# spider.net
KiCad netlist of a schematic drawn in Altium Designer
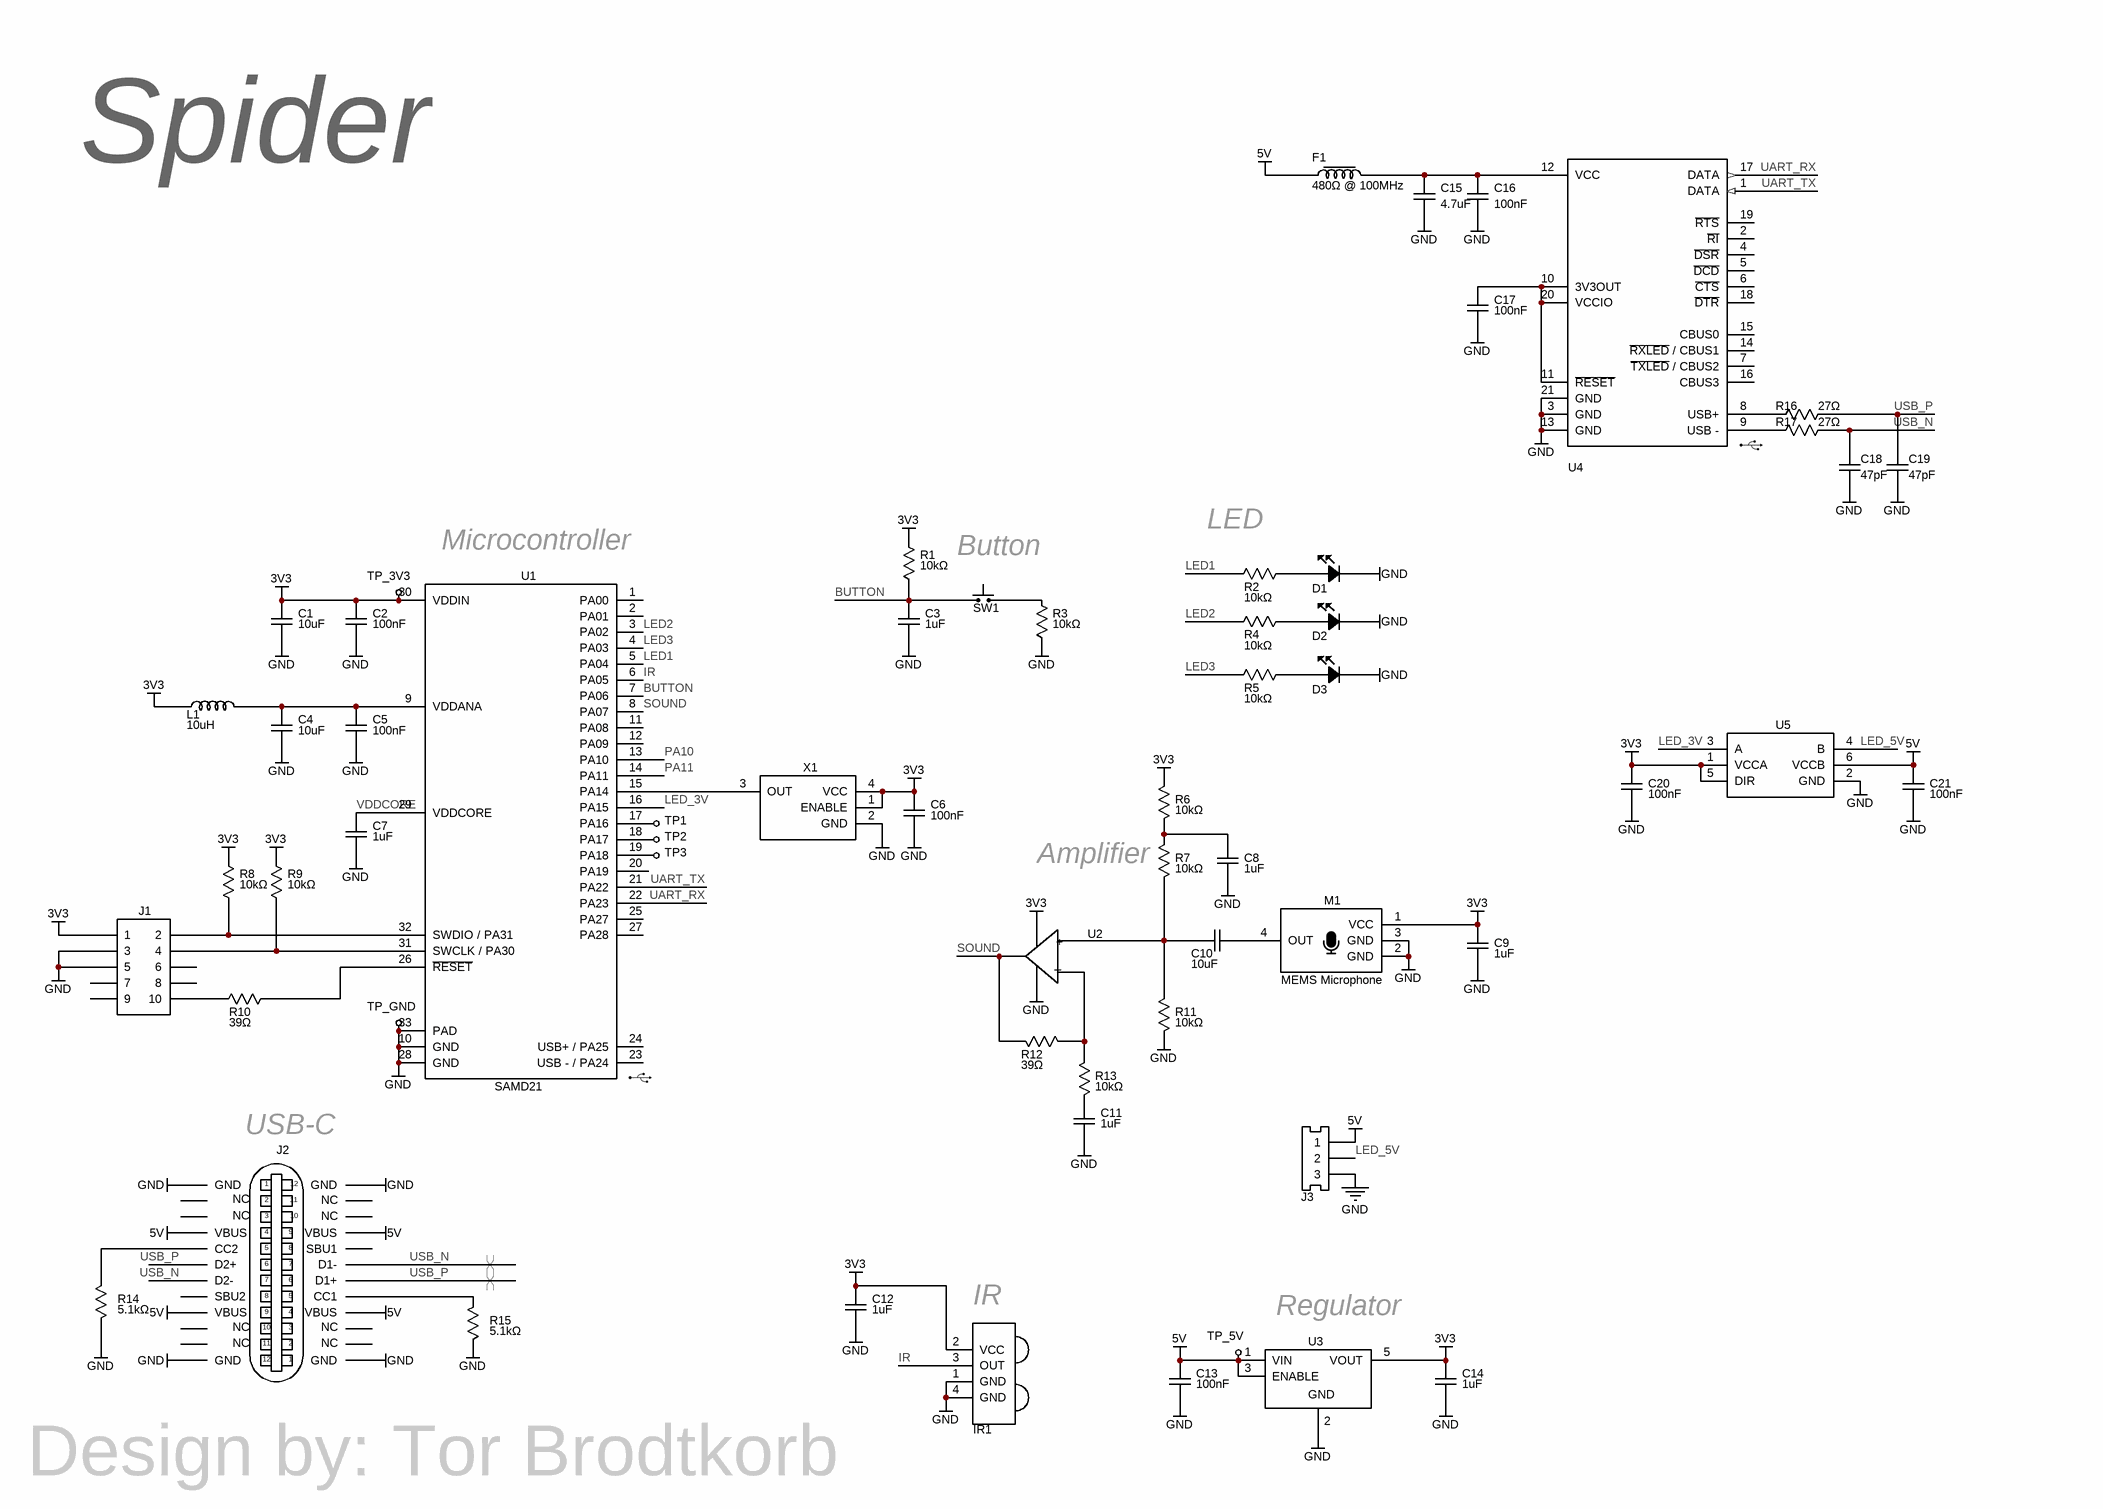
[diagram p0: spider.SchDoc]

(export (version "E")
  (design (tool "Eeschema 10.0.6"))
  (components
    (comp (ref "C1")
      (value "10uF")
      (footprint "capacitor 0603")
      (description "Capacitor 0603")
      (fields (field (name "Comment") "passive_5"))
      (libsource (lib "passive") (part "passive_5"))
    )
    (comp (ref "C2")
      (value "100nF")
      (footprint "capacitor 0603")
      (description "Capacitor 0603")
      (fields (field (name "Comment") "passive_5"))
      (libsource (lib "passive") (part "passive_5"))
    )
    (comp (ref "C3")
      (value "1uF")
      (footprint "capacitor 0603")
      (description "Capacitor 0603")
      (fields (field (name "Comment") "passive_5"))
      (libsource (lib "passive") (part "passive_5"))
    )
    (comp (ref "C4")
      (value "10uF")
      (footprint "capacitor 0603")
      (description "Capacitor 0603")
      (fields (field (name "Comment") "passive_5"))
      (libsource (lib "passive") (part "passive_5"))
    )
    (comp (ref "C5")
      (value "100nF")
      (footprint "capacitor 0603")
      (description "Capacitor 0603")
      (fields (field (name "Comment") "passive_5"))
      (libsource (lib "passive") (part "passive_5"))
    )
    (comp (ref "C6")
      (value "100nF")
      (footprint "capacitor 0603")
      (description "Capacitor 0603")
      (fields (field (name "Comment") "passive_5"))
      (libsource (lib "passive") (part "passive_5"))
    )
    (comp (ref "C7")
      (value "1uF")
      (footprint "capacitor 0603")
      (description "Capacitor 0603")
      (fields (field (name "Comment") "passive_5"))
      (libsource (lib "passive") (part "passive_5"))
    )
    (comp (ref "C8")
      (value "1uF")
      (footprint "capacitor 0603")
      (description "Capacitor 0603")
      (fields (field (name "Comment") "passive_5"))
      (libsource (lib "passive") (part "passive_5"))
    )
    (comp (ref "C9")
      (value "1uF")
      (footprint "capacitor 0603")
      (description "Capacitor 0603")
      (fields (field (name "Comment") "passive_5"))
      (libsource (lib "passive") (part "passive_5"))
    )
    (comp (ref "C10")
      (value "10uF")
      (footprint "capacitor 0603")
      (description "Capacitor 0603")
      (fields (field (name "Comment") "passive_5"))
      (libsource (lib "passive") (part "passive_5"))
    )
    (comp (ref "C11")
      (value "1uF")
      (footprint "capacitor 0603")
      (description "Capacitor 0603")
      (fields (field (name "Comment") "passive_5"))
      (libsource (lib "passive") (part "passive_5"))
    )
    (comp (ref "C12")
      (value "1uF")
      (footprint "capacitor 0603")
      (description "Capacitor 0603")
      (fields (field (name "Comment") "passive_5"))
      (libsource (lib "passive") (part "passive_5"))
    )
    (comp (ref "C13")
      (value "100nF")
      (footprint "capacitor 0603")
      (description "Capacitor 0603")
      (fields (field (name "Comment") "passive_5"))
      (libsource (lib "passive") (part "passive_5"))
    )
    (comp (ref "C14")
      (value "1uF")
      (footprint "capacitor 0603")
      (description "Capacitor 0603")
      (fields (field (name "Comment") "passive_5"))
      (libsource (lib "passive") (part "passive_5"))
    )
    (comp (ref "C15")
      (value "4.7uF")
      (footprint "capacitor 0603")
      (description "Capacitor 0603")
      (fields (field (name "Comment") "passive_5"))
      (libsource (lib "passive") (part "passive_5"))
    )
    (comp (ref "C16")
      (value "100nF")
      (footprint "capacitor 0603")
      (description "Capacitor 0603")
      (fields (field (name "Comment") "passive_5"))
      (libsource (lib "passive") (part "passive_5"))
    )
    (comp (ref "C17")
      (value "100nF")
      (footprint "capacitor 0603")
      (description "Capacitor 0603")
      (fields (field (name "Comment") "passive_5"))
      (libsource (lib "passive") (part "passive_5"))
    )
    (comp (ref "C18")
      (value "47pF")
      (footprint "capacitor 0603")
      (description "Capacitor 0603")
      (fields (field (name "Comment") "passive_5"))
      (libsource (lib "passive") (part "passive_5"))
    )
    (comp (ref "C19")
      (value "47pF")
      (footprint "capacitor 0603")
      (description "Capacitor 0603")
      (fields (field (name "Comment") "passive_5"))
      (libsource (lib "passive") (part "passive_5"))
    )
    (comp (ref "C20")
      (value "100nF")
      (footprint "capacitor 0603")
      (description "Capacitor 0603")
      (fields (field (name "Comment") "passive_5"))
      (libsource (lib "passive") (part "passive_5"))
    )
    (comp (ref "C21")
      (value "100nF")
      (footprint "capacitor 0603")
      (description "Capacitor 0603")
      (fields (field (name "Comment") "passive_5"))
      (libsource (lib "passive") (part "passive_5"))
    )
    (comp (ref "D1")
      (value "LED White")
      (footprint "LED 0603 white")
      (description "LED 0603 white")
      (libsource (lib "diode") (part "diode_6"))
    )
    (comp (ref "D2")
      (value "LED White")
      (footprint "LED 0603 white")
      (description "LED 0603 white")
      (libsource (lib "diode") (part "diode_6"))
    )
    (comp (ref "D3")
      (value "LED White")
      (footprint "LED 0603 white")
      (description "LED 0603 white")
      (libsource (lib "diode") (part "diode_6"))
    )
    (comp (ref "F1")
      (value "480Ω @ 100MHz")
      (footprint "ferrit bead 0603")
      (description "Ferrite bead 0603")
      (fields (field (name "Comment") "passive_8"))
      (libsource (lib "passive") (part "passive_8"))
    )
    (comp (ref "IR1")
      (value "sensor_1")
      (footprint "TSSP77038TR")
      (description "IR receiver, 38 kHz, 40m, SMD")
      (libsource (lib "sensor") (part "sensor_1"))
    )
    (comp (ref "J1")
      (value "Header 1.27mm")
      (footprint "header male 2x5, pitch 1.27mm")
      (description "Header male 2x5, pitch 1.27mm")
      (libsource (lib "connector") (part "connector_17"))
    )
    (comp (ref "J2")
      (value "USB 2.0")
      (footprint "USB4105-GF-A")
      (description "USB-C (2.0)")
      (libsource (lib "connector") (part "connector_35"))
    )
    (comp (ref "J3")
      (value "connector_41")
      (footprint "S3B-XH-A (LF)(SN)")
      (description "JST connector 1x3, pitch 2.5mm, right angle, TH")
      (libsource (lib "connector") (part "connector_41"))
    )
    (comp (ref "L1")
      (value "10uH")
      (footprint "inductor 0603")
      (description "Inductor 0603")
      (fields (field (name "Comment") "passive_9"))
      (libsource (lib "passive") (part "passive_9"))
    )
    (comp (ref "M1")
      (value "MEMS Microphone")
      (footprint "SPU0410HR5H-PB")
      (description "Microphone, MEMS, 100 Hz - 10 kHz, 3.3V,  SMD")
      (libsource (lib "sensor") (part "sensor_2"))
    )
    (comp (ref "R1")
      (value "10kΩ")
      (footprint "resistor 0603")
      (description "Resistor 0603")
      (fields (field (name "Comment") "passive_2"))
      (libsource (lib "passive") (part "passive_2"))
    )
    (comp (ref "R2")
      (value "10kΩ")
      (footprint "resistor 0603")
      (description "Resistor 0603")
      (fields (field (name "Comment") "passive_2"))
      (libsource (lib "passive") (part "passive_2"))
    )
    (comp (ref "R3")
      (value "10kΩ")
      (footprint "resistor 0603")
      (description "Resistor 0603")
      (fields (field (name "Comment") "passive_2"))
      (libsource (lib "passive") (part "passive_2"))
    )
    (comp (ref "R4")
      (value "10kΩ")
      (footprint "resistor 0603")
      (description "Resistor 0603")
      (fields (field (name "Comment") "passive_2"))
      (libsource (lib "passive") (part "passive_2"))
    )
    (comp (ref "R5")
      (value "10kΩ")
      (footprint "resistor 0603")
      (description "Resistor 0603")
      (fields (field (name "Comment") "passive_2"))
      (libsource (lib "passive") (part "passive_2"))
    )
    (comp (ref "R6")
      (value "10kΩ")
      (footprint "resistor 0603")
      (description "Resistor 0603")
      (fields (field (name "Comment") "passive_2"))
      (libsource (lib "passive") (part "passive_2"))
    )
    (comp (ref "R7")
      (value "10kΩ")
      (footprint "resistor 0603")
      (description "Resistor 0603")
      (fields (field (name "Comment") "passive_2"))
      (libsource (lib "passive") (part "passive_2"))
    )
    (comp (ref "R8")
      (value "10kΩ")
      (footprint "resistor 0603")
      (description "Resistor 0603")
      (fields (field (name "Comment") "passive_2"))
      (libsource (lib "passive") (part "passive_2"))
    )
    (comp (ref "R9")
      (value "10kΩ")
      (footprint "resistor 0603")
      (description "Resistor 0603")
      (fields (field (name "Comment") "passive_2"))
      (libsource (lib "passive") (part "passive_2"))
    )
    (comp (ref "R10")
      (value "39Ω")
      (footprint "resistor 0603")
      (description "Resistor 0603")
      (fields (field (name "Comment") "passive_2"))
      (libsource (lib "passive") (part "passive_2"))
    )
    (comp (ref "R11")
      (value "10kΩ")
      (footprint "resistor 0603")
      (description "Resistor 0603")
      (fields (field (name "Comment") "passive_2"))
      (libsource (lib "passive") (part "passive_2"))
    )
    (comp (ref "R12")
      (value "39Ω")
      (footprint "resistor 0603")
      (description "Resistor 0603")
      (fields (field (name "Comment") "passive_2"))
      (libsource (lib "passive") (part "passive_2"))
    )
    (comp (ref "R13")
      (value "10kΩ")
      (footprint "resistor 0603")
      (description "Resistor 0603")
      (fields (field (name "Comment") "passive_2"))
      (libsource (lib "passive") (part "passive_2"))
    )
    (comp (ref "R14")
      (value "5.1kΩ")
      (footprint "resistor 0603")
      (description "Resistor 0603")
      (fields (field (name "Comment") "passive_2"))
      (libsource (lib "passive") (part "passive_2"))
    )
    (comp (ref "R15")
      (value "5.1kΩ")
      (footprint "resistor 0603")
      (description "Resistor 0603")
      (fields (field (name "Comment") "passive_2"))
      (libsource (lib "passive") (part "passive_2"))
    )
    (comp (ref "R16")
      (value "27Ω")
      (footprint "resistor 0603")
      (description "Resistor 0603")
      (fields (field (name "Comment") "passive_2"))
      (libsource (lib "passive") (part "passive_2"))
    )
    (comp (ref "R17")
      (value "27Ω")
      (footprint "resistor 0603")
      (description "Resistor 0603")
      (fields (field (name "Comment") "passive_2"))
      (libsource (lib "passive") (part "passive_2"))
    )
    (comp (ref "SW1")
      (value "connector_35")
      (footprint "KMR621NG LFS")
      (description "Tactile switch SMD, tiny")
      (libsource (lib "sensor") (part "connector_35"))
    )
    (comp (ref "TP1")
      (value "misc_3")
      (footprint "testpoint round, diameter 1.5mm")
      (description "Test-point round, diameter 1.5mm")
      (libsource (lib "miscellaneous") (part "misc_3"))
    )
    (comp (ref "TP2")
      (value "misc_3")
      (footprint "testpoint round, diameter 1.5mm")
      (description "Test-point round, diameter 1.5mm")
      (libsource (lib "miscellaneous") (part "misc_3"))
    )
    (comp (ref "TP3")
      (value "misc_3")
      (footprint "testpoint round, diameter 1.5mm")
      (description "Test-point round, diameter 1.5mm")
      (libsource (lib "miscellaneous") (part "misc_3"))
    )
    (comp (ref "TP_3V3")
      (value "misc_3")
      (footprint "testpoint round, diameter 1.5mm")
      (description "Test-point round, diameter 1.5mm")
      (libsource (lib "miscellaneous") (part "misc_3"))
    )
    (comp (ref "TP_5V")
      (value "misc_3")
      (footprint "testpoint round, diameter 1.5mm")
      (description "Test-point round, diameter 1.5mm")
      (libsource (lib "miscellaneous") (part "misc_3"))
    )
    (comp (ref "TP_GND")
      (value "misc_3")
      (footprint "testpoint round, diameter 1.5mm")
      (description "Test-point round, diameter 1.5mm")
      (libsource (lib "miscellaneous") (part "misc_3"))
    )
    (comp (ref "U1")
      (value "SAMD21")
      (footprint "ATSAMD21E17D-MUT")
      (description "SAMD21, 48 MHz, 128KB flash, 16KB RAM, 32 pins, USB device, QFN")
      (libsource (lib "cpu") (part "cpu_0"))
    )
    (comp (ref "U2")
      (value "ic_6")
      (footprint "MCP6241T-E/OT")
      (description "OpAmp, 1 circuit, rail-to-rail, single supply, 1.8V to 5V, SOT23-5")
      (libsource (lib "integrated-circuit") (part "ic_6"))
    )
    (comp (ref "U3")
      (value "regulator_1")
      (footprint "TCR2EF33,LM(CT")
      (description "LDO fixed, 3.3V output, 0.2V dropout, 200mA")
      (libsource (lib "voltage-regulator") (part "regulator_1"))
    )
    (comp (ref "U4")
      (value "FTDI")
      (footprint "FT231XQ-R")
      (description "USB to UART converter, FTDI, single, 20 pins, QFN")
      (libsource (lib "integrated-circuit") (part "ic_1"))
    )
    (comp (ref "U5")
      (value "ic_10")
      (footprint "74LVC1T45Z6-7")
      (description "Level shifter, bidirectional, 1.65V - 5V, SOT-563")
      (libsource (lib "integrated-circuit") (part "ic_10"))
    )
    (comp (ref "X1")
      (value "8 MHz")
      (footprint "DSC6001CE2A-008.0000")
      (description "Oscillator, 8MHz, 3.3V, 3.2mm x 2.5mm")
      (libsource (lib "oscillator") (part "oscillator_2"))
    )
  )
  (nets
    (net (code "1") (name "/BUTTON") (class "Default")
      (node (ref "C3") (pin "2") (pinfunction "2_2") (pintype "passive"))
      (node (ref "R1") (pin "2") (pinfunction "2_2") (pintype "passive"))
      (node (ref "SW1") (pin "1") (pintype "passive"))
      (node (ref "U1") (pin "7") (pinfunction "PA06_7") (pintype "passive"))
    )
    (net (code "2") (name "/IR") (class "Default")
      (node (ref "IR1") (pin "3") (pinfunction "OUT_3") (pintype "passive"))
      (node (ref "U1") (pin "6") (pinfunction "PA05_6") (pintype "passive"))
    )
    (net (code "3") (name "/LED1") (class "Default")
      (node (ref "R2") (pin "2") (pinfunction "2_2") (pintype "passive"))
      (node (ref "U1") (pin "5") (pinfunction "PA04_5") (pintype "passive"))
    )
    (net (code "4") (name "/LED2") (class "Default")
      (node (ref "R4") (pin "2") (pinfunction "2_2") (pintype "passive"))
      (node (ref "U1") (pin "3") (pinfunction "PA02_3") (pintype "passive"))
    )
    (net (code "5") (name "/LED3") (class "Default")
      (node (ref "R5") (pin "2") (pinfunction "2_2") (pintype "passive"))
      (node (ref "U1") (pin "4") (pinfunction "PA03_4") (pintype "passive"))
    )
    (net (code "6") (name "/LED_3V") (class "Default")
      (node (ref "U1") (pin "16") (pinfunction "PA15_16") (pintype "passive"))
      (node (ref "U5") (pin "3") (pinfunction "A_3") (pintype "passive"))
    )
    (net (code "7") (name "/LED_5V") (class "Default")
      (node (ref "J3") (pin "2") (pinfunction "2_2") (pintype "passive"))
      (node (ref "U5") (pin "4") (pinfunction "B_4") (pintype "passive"))
    )
    (net (code "8") (name "/PA10") (class "Default")
      (node (ref "U1") (pin "13") (pinfunction "PA10_13") (pintype "passive"))
    )
    (net (code "9") (name "/PA11") (class "Default")
      (node (ref "U1") (pin "14") (pinfunction "PA11_14") (pintype "passive"))
    )
    (net (code "10") (name "/SOUND") (class "Default")
      (node (ref "R12") (pin "2") (pinfunction "2_2") (pintype "passive"))
      (node (ref "U1") (pin "8") (pinfunction "PA07_8") (pintype "passive"))
      (node (ref "U2") (pin "1") (pintype "passive"))
    )
    (net (code "11") (name "/UART_RX") (class "Default")
      (node (ref "U1") (pin "22") (pinfunction "PA23_22") (pintype "passive"))
      (node (ref "U4") (pin "17") (pinfunction "DATA_17") (pintype "passive"))
    )
    (net (code "12") (name "/UART_TX") (class "Default")
      (node (ref "U1") (pin "21") (pinfunction "PA22_21") (pintype "passive"))
      (node (ref "U4") (pin "1") (pinfunction "DATA_1") (pintype "passive"))
    )
    (net (code "13") (name "/USB_N") (class "Default")
      (node (ref "C18") (pin "2") (pinfunction "2_2") (pintype "passive"))
      (node (ref "J2") (pin "A7") (pinfunction "D1-_A7") (pintype "passive"))
      (node (ref "J2") (pin "B7") (pinfunction "D2-_B7") (pintype "passive"))
      (node (ref "R17") (pin "2") (pinfunction "2_2") (pintype "passive"))
    )
    (net (code "14") (name "/USB_P") (class "Default")
      (node (ref "C19") (pin "2") (pinfunction "2_2") (pintype "passive"))
      (node (ref "J2") (pin "A6") (pinfunction "D1+_A6") (pintype "passive"))
      (node (ref "J2") (pin "B6") (pinfunction "D2+_B6") (pintype "passive"))
      (node (ref "R16") (pin "2") (pinfunction "2_2") (pintype "passive"))
    )
    (net (code "15") (name "/VDDCORE") (class "Default")
      (node (ref "C7") (pin "2") (pinfunction "2_2") (pintype "passive"))
      (node (ref "U1") (pin "29") (pinfunction "VDDCORE_29") (pintype "passive"))
    )
    (net (code "16") (name "3V3") (class "Default")
      (node (ref "C1") (pin "2") (pinfunction "2_2") (pintype "passive"))
      (node (ref "C12") (pin "2") (pinfunction "2_2") (pintype "passive"))
      (node (ref "C14") (pin "2") (pinfunction "2_2") (pintype "passive"))
      (node (ref "C2") (pin "2") (pinfunction "2_2") (pintype "passive"))
      (node (ref "C20") (pin "2") (pinfunction "2_2") (pintype "passive"))
      (node (ref "C6") (pin "2") (pinfunction "2_2") (pintype "passive"))
      (node (ref "C9") (pin "2") (pinfunction "2_2") (pintype "passive"))
      (node (ref "IR1") (pin "2") (pinfunction "VCC_2") (pintype "passive"))
      (node (ref "J1") (pin "1") (pinfunction "1_1") (pintype "passive"))
      (node (ref "L1") (pin "1") (pintype "passive"))
      (node (ref "M1") (pin "1") (pinfunction "VCC_1") (pintype "passive"))
      (node (ref "R1") (pin "1") (pintype "passive"))
      (node (ref "R6") (pin "2") (pinfunction "2_2") (pintype "passive"))
      (node (ref "R8") (pin "2") (pinfunction "2_2") (pintype "passive"))
      (node (ref "R9") (pin "2") (pinfunction "2_2") (pintype "passive"))
      (node (ref "TP_3V3") (pin "1") (pintype "passive"))
      (node (ref "U1") (pin "30") (pinfunction "VDDIN_30") (pintype "passive"))
      (node (ref "U2") (pin "5") (pintype "passive"))
      (node (ref "U3") (pin "5") (pinfunction "VOUT_5") (pintype "passive"))
      (node (ref "U5") (pin "1") (pinfunction "VCCA_1") (pintype "passive"))
      (node (ref "U5") (pin "5") (pinfunction "DIR_5") (pintype "passive"))
      (node (ref "X1") (pin "1") (pinfunction "ENABLE_1") (pintype "passive"))
      (node (ref "X1") (pin "4") (pinfunction "VCC_4") (pintype "passive"))
    )
    (net (code "17") (name "5V") (class "Default")
      (node (ref "C13") (pin "2") (pinfunction "2_2") (pintype "passive"))
      (node (ref "C21") (pin "2") (pinfunction "2_2") (pintype "passive"))
      (node (ref "F1") (pin "1") (pintype "passive"))
      (node (ref "J2") (pin "A4_B9") (pinfunction "VBUS_A4_B9") (pintype "passive"))
      (node (ref "J2") (pin "B4_A9") (pinfunction "VBUS_B4_A9") (pintype "passive"))
      (node (ref "J3") (pin "1") (pinfunction "1_1") (pintype "passive"))
      (node (ref "TP_5V") (pin "1") (pintype "passive"))
      (node (ref "U3") (pin "1") (pinfunction "VIN_1") (pintype "passive"))
      (node (ref "U3") (pin "3") (pinfunction "ENABLE_3") (pintype "passive"))
      (node (ref "U5") (pin "6") (pinfunction "VCCB_6") (pintype "passive"))
    )
    (net (code "18") (name "GND") (class "Default")
      (node (ref "C1") (pin "1") (pinfunction "1_1") (pintype "passive"))
      (node (ref "C11") (pin "1") (pinfunction "1_1") (pintype "passive"))
      (node (ref "C12") (pin "1") (pinfunction "1_1") (pintype "passive"))
      (node (ref "C13") (pin "1") (pinfunction "1_1") (pintype "passive"))
      (node (ref "C14") (pin "1") (pinfunction "1_1") (pintype "passive"))
      (node (ref "C15") (pin "1") (pinfunction "1_1") (pintype "passive"))
      (node (ref "C16") (pin "1") (pinfunction "1_1") (pintype "passive"))
      (node (ref "C17") (pin "1") (pinfunction "1_1") (pintype "passive"))
      (node (ref "C18") (pin "1") (pinfunction "1_1") (pintype "passive"))
      (node (ref "C19") (pin "1") (pinfunction "1_1") (pintype "passive"))
      (node (ref "C2") (pin "1") (pinfunction "1_1") (pintype "passive"))
      (node (ref "C20") (pin "1") (pinfunction "1_1") (pintype "passive"))
      (node (ref "C21") (pin "1") (pinfunction "1_1") (pintype "passive"))
      (node (ref "C3") (pin "1") (pinfunction "1_1") (pintype "passive"))
      (node (ref "C4") (pin "1") (pinfunction "1_1") (pintype "passive"))
      (node (ref "C5") (pin "1") (pinfunction "1_1") (pintype "passive"))
      (node (ref "C6") (pin "1") (pinfunction "1_1") (pintype "passive"))
      (node (ref "C7") (pin "1") (pinfunction "1_1") (pintype "passive"))
      (node (ref "C8") (pin "1") (pinfunction "1_1") (pintype "passive"))
      (node (ref "C9") (pin "1") (pinfunction "1_1") (pintype "passive"))
      (node (ref "D1") (pin "2") (pinfunction "2_2") (pintype "passive"))
      (node (ref "D2") (pin "2") (pinfunction "2_2") (pintype "passive"))
      (node (ref "D3") (pin "2") (pinfunction "2_2") (pintype "passive"))
      (node (ref "IR1") (pin "1") (pinfunction "GND_1") (pintype "passive"))
      (node (ref "IR1") (pin "4") (pinfunction "GND_4") (pintype "passive"))
      (node (ref "J1") (pin "3") (pinfunction "3_3") (pintype "passive"))
      (node (ref "J1") (pin "5") (pinfunction "5_5") (pintype "passive"))
      (node (ref "J2") (pin "A1_B12") (pinfunction "GND_A1_B12") (pintype "passive"))
      (node (ref "J2") (pin "B1_A12") (pinfunction "GND_B1_A12") (pintype "passive"))
      (node (ref "J3") (pin "3") (pinfunction "3_3") (pintype "passive"))
      (node (ref "M1") (pin "2") (pinfunction "GND_2") (pintype "passive"))
      (node (ref "M1") (pin "3") (pinfunction "GND_3") (pintype "passive"))
      (node (ref "R11") (pin "1") (pintype "passive"))
      (node (ref "R14") (pin "1") (pintype "passive"))
      (node (ref "R15") (pin "1") (pintype "passive"))
      (node (ref "R3") (pin "2") (pinfunction "2_2") (pintype "passive"))
      (node (ref "TP_GND") (pin "1") (pintype "passive"))
      (node (ref "U1") (pin "10") (pinfunction "GND_10") (pintype "passive"))
      (node (ref "U1") (pin "28") (pinfunction "GND_28") (pintype "passive"))
      (node (ref "U1") (pin "33") (pinfunction "PAD_33") (pintype "passive"))
      (node (ref "U2") (pin "2") (pintype "passive"))
      (node (ref "U3") (pin "2") (pintype "passive"))
      (node (ref "U4") (pin "13") (pinfunction "GND_13") (pintype "passive"))
      (node (ref "U4") (pin "21") (pinfunction "GND_21") (pintype "passive"))
      (node (ref "U4") (pin "3") (pinfunction "GND_3") (pintype "passive"))
      (node (ref "U5") (pin "2") (pinfunction "GND_2") (pintype "passive"))
      (node (ref "X1") (pin "2") (pinfunction "GND_2") (pintype "passive"))
    )
    (net (code "19") (name "Net-(C8-Pad2)") (class "Default")
      (node (ref "C8") (pin "2") (pinfunction "2_2") (pintype "passive"))
      (node (ref "R6") (pin "1") (pintype "passive"))
      (node (ref "R7") (pin "2") (pinfunction "2_2") (pintype "passive"))
    )
    (net (code "20") (name "Net-(C10-Pad1)") (class "Default")
      (node (ref "C10") (pin "1") (pinfunction "1_1") (pintype "passive"))
      (node (ref "R11") (pin "2") (pinfunction "2_2") (pintype "passive"))
      (node (ref "R7") (pin "1") (pintype "passive"))
      (node (ref "U2") (pin "3") (pintype "passive"))
    )
    (net (code "21") (name "Net-(C11-Pad2)") (class "Default")
      (node (ref "C11") (pin "2") (pinfunction "2_2") (pintype "passive"))
      (node (ref "R13") (pin "1") (pintype "passive"))
    )
    (net (code "22") (name "Net-(D1-Pad1)") (class "Default")
      (node (ref "D1") (pin "1") (pinfunction "1_1") (pintype "passive"))
      (node (ref "R2") (pin "1") (pintype "passive"))
    )
    (net (code "23") (name "Net-(D2-Pad1)") (class "Default")
      (node (ref "D2") (pin "1") (pinfunction "1_1") (pintype "passive"))
      (node (ref "R4") (pin "1") (pintype "passive"))
    )
    (net (code "24") (name "Net-(D3-Pad1)") (class "Default")
      (node (ref "D3") (pin "1") (pinfunction "1_1") (pintype "passive"))
      (node (ref "R5") (pin "1") (pintype "passive"))
    )
    (net (code "25") (name "Net-(J1-Pad10)") (class "Default")
      (node (ref "J1") (pin "10") (pinfunction "10_10") (pintype "passive"))
      (node (ref "R10") (pin "1") (pintype "passive"))
    )
    (net (code "26") (name "Net-(J2-CC1)") (class "Default")
      (node (ref "J2") (pin "A5") (pinfunction "CC1_A5") (pintype "passive"))
      (node (ref "R15") (pin "2") (pinfunction "2_2") (pintype "passive"))
    )
    (net (code "27") (name "Net-(J2-CC2)") (class "Default")
      (node (ref "J2") (pin "B5") (pinfunction "CC2_B5") (pintype "passive"))
      (node (ref "R14") (pin "2") (pinfunction "2_2") (pintype "passive"))
    )
    (net (code "28") (name "Net-(M1-OUT)") (class "Default")
      (node (ref "C10") (pin "2") (pinfunction "2_2") (pintype "passive"))
      (node (ref "M1") (pin "4") (pinfunction "OUT_4") (pintype "passive"))
    )
    (net (code "29") (name "Net-(R3-Pad1)") (class "Default")
      (node (ref "R3") (pin "1") (pintype "passive"))
      (node (ref "SW1") (pin "2") (pintype "passive"))
    )
    (net (code "30") (name "Net-(R12-Pad1)") (class "Default")
      (node (ref "R12") (pin "1") (pintype "passive"))
      (node (ref "R13") (pin "2") (pinfunction "2_2") (pintype "passive"))
      (node (ref "U2") (pin "4") (pintype "passive"))
    )
    (net (code "31") (name "Net-(U1-PA14)") (class "Default")
      (node (ref "U1") (pin "15") (pinfunction "PA14_15") (pintype "passive"))
      (node (ref "X1") (pin "3") (pinfunction "OUT_3") (pintype "passive"))
    )
    (net (code "32") (name "Net-(U1-PA16)") (class "Default")
      (node (ref "TP1") (pin "1") (pintype "passive"))
      (node (ref "U1") (pin "17") (pinfunction "PA16_17") (pintype "passive"))
    )
    (net (code "33") (name "Net-(U1-PA17)") (class "Default")
      (node (ref "TP2") (pin "1") (pintype "passive"))
      (node (ref "U1") (pin "18") (pinfunction "PA17_18") (pintype "passive"))
    )
    (net (code "34") (name "Net-(U1-PA18)") (class "Default")
      (node (ref "TP3") (pin "1") (pintype "passive"))
      (node (ref "U1") (pin "19") (pinfunction "PA18_19") (pintype "passive"))
    )
    (net (code "35") (name "Net-(U1-SWCLK_{slash}_PA30)") (class "Default")
      (node (ref "J1") (pin "4") (pinfunction "4_4") (pintype "passive"))
      (node (ref "R9") (pin "1") (pintype "passive"))
      (node (ref "U1") (pin "31") (pinfunction "SWCLK_/_PA30_31") (pintype "passive"))
    )
    (net (code "36") (name "Net-(U1-SWDIO_{slash}_PA31)") (class "Default")
      (node (ref "J1") (pin "2") (pinfunction "2_2") (pintype "passive"))
      (node (ref "R8") (pin "1") (pintype "passive"))
      (node (ref "U1") (pin "32") (pinfunction "SWDIO_/_PA31_32") (pintype "passive"))
    )
    (net (code "37") (name "Net-(U1-VDDANA)") (class "Default")
      (node (ref "C4") (pin "2") (pinfunction "2_2") (pintype "passive"))
      (node (ref "C5") (pin "2") (pinfunction "2_2") (pintype "passive"))
      (node (ref "L1") (pin "2") (pinfunction "2_2") (pintype "passive"))
      (node (ref "U1") (pin "9") (pinfunction "VDDANA_9") (pintype "passive"))
    )
    (net (code "38") (name "Net-(U1-~{RESET})") (class "Default")
      (node (ref "R10") (pin "2") (pinfunction "2_2") (pintype "passive"))
      (node (ref "U1") (pin "26") (pinfunction "~{RESET}_26") (pintype "passive"))
    )
    (net (code "39") (name "Net-(U4-3V3OUT)") (class "Default")
      (node (ref "C17") (pin "2") (pinfunction "2_2") (pintype "passive"))
      (node (ref "U4") (pin "10") (pinfunction "3V3OUT_10") (pintype "passive"))
      (node (ref "U4") (pin "11") (pinfunction "~{RESET}_11") (pintype "passive"))
      (node (ref "U4") (pin "20") (pinfunction "VCCIO_20") (pintype "passive"))
    )
    (net (code "40") (name "Net-(U4-USB+)") (class "Default")
      (node (ref "R16") (pin "1") (pintype "passive"))
      (node (ref "U4") (pin "8") (pinfunction "USB+_8") (pintype "passive"))
    )
    (net (code "41") (name "Net-(U4-USB_-)") (class "Default")
      (node (ref "R17") (pin "1") (pintype "passive"))
      (node (ref "U4") (pin "9") (pinfunction "USB_-_9") (pintype "passive"))
    )
    (net (code "42") (name "Net-(U4-VCC)") (class "Default")
      (node (ref "C15") (pin "2") (pinfunction "2_2") (pintype "passive"))
      (node (ref "C16") (pin "2") (pinfunction "2_2") (pintype "passive"))
      (node (ref "F1") (pin "2") (pinfunction "2_2") (pintype "passive"))
      (node (ref "U4") (pin "12") (pinfunction "VCC_12") (pintype "passive"))
    )
    (net (code "43") (name "unconnected-(J1-Pad6)") (class "Default")
      (node (ref "J1") (pin "6") (pinfunction "6_6") (pintype "passive"))
    )
    (net (code "44") (name "unconnected-(J1-Pad7)") (class "Default")
      (node (ref "J1") (pin "7") (pinfunction "7_7") (pintype "passive"))
    )
    (net (code "45") (name "unconnected-(J1-Pad8)") (class "Default")
      (node (ref "J1") (pin "8") (pinfunction "8_8") (pintype "passive"))
    )
    (net (code "46") (name "unconnected-(J1-Pad9)") (class "Default")
      (node (ref "J1") (pin "9") (pinfunction "9_9") (pintype "passive"))
    )
    (net (code "47") (name "unconnected-(J2-SBU1-PadA8)") (class "Default")
      (node (ref "J2") (pin "A8") (pinfunction "SBU1_A8") (pintype "passive"))
    )
    (net (code "48") (name "unconnected-(J2-SBU2-PadB8)") (class "Default")
      (node (ref "J2") (pin "B8") (pinfunction "SBU2_B8") (pintype "passive"))
    )
    (net (code "49") (name "unconnected-(U1-PA00-Pad1)") (class "Default")
      (node (ref "U1") (pin "1") (pinfunction "PA00_1") (pintype "passive"))
    )
    (net (code "50") (name "unconnected-(U1-PA01-Pad2)") (class "Default")
      (node (ref "U1") (pin "2") (pinfunction "PA01_2") (pintype "passive"))
    )
    (net (code "51") (name "unconnected-(U1-PA08-Pad11)") (class "Default")
      (node (ref "U1") (pin "11") (pinfunction "PA08_11") (pintype "passive"))
    )
    (net (code "52") (name "unconnected-(U1-PA09-Pad12)") (class "Default")
      (node (ref "U1") (pin "12") (pinfunction "PA09_12") (pintype "passive"))
    )
    (net (code "53") (name "unconnected-(U1-PA19-Pad20)") (class "Default")
      (node (ref "U1") (pin "20") (pinfunction "PA19_20") (pintype "passive"))
    )
    (net (code "54") (name "unconnected-(U1-PA27-Pad25)") (class "Default")
      (node (ref "U1") (pin "25") (pinfunction "PA27_25") (pintype "passive"))
    )
    (net (code "55") (name "unconnected-(U1-PA28-Pad27)") (class "Default")
      (node (ref "U1") (pin "27") (pinfunction "PA28_27") (pintype "passive"))
    )
    (net (code "56") (name "unconnected-(U1-USB+_{slash}_PA25-Pad24)") (class "Default")
      (node (ref "U1") (pin "24") (pinfunction "USB+_/_PA25_24") (pintype "passive"))
    )
    (net (code "57") (name "unconnected-(U1-USB_-_{slash}_PA24-Pad23)") (class "Default")
      (node (ref "U1") (pin "23") (pinfunction "USB_-_/_PA24_23") (pintype "passive"))
    )
    (net (code "58") (name "unconnected-(U4-CBUS0-Pad15)") (class "Default")
      (node (ref "U4") (pin "15") (pinfunction "CBUS0_15") (pintype "passive"))
    )
    (net (code "59") (name "unconnected-(U4-CBUS3-Pad16)") (class "Default")
      (node (ref "U4") (pin "16") (pinfunction "CBUS3_16") (pintype "passive"))
    )
    (net (code "60") (name "unconnected-(U4-~{CTS}-Pad6)") (class "Default")
      (node (ref "U4") (pin "6") (pinfunction "~{CTS}_6") (pintype "passive"))
    )
    (net (code "61") (name "unconnected-(U4-~{DCD}-Pad5)") (class "Default")
      (node (ref "U4") (pin "5") (pinfunction "~{DCD}_5") (pintype "passive"))
    )
    (net (code "62") (name "unconnected-(U4-~{DSR}-Pad4)") (class "Default")
      (node (ref "U4") (pin "4") (pinfunction "~{DSR}_4") (pintype "passive"))
    )
    (net (code "63") (name "unconnected-(U4-~{DTR}-Pad18)") (class "Default")
      (node (ref "U4") (pin "18") (pinfunction "~{DTR}_18") (pintype "passive"))
    )
    (net (code "64") (name "unconnected-(U4-~{RI}-Pad2)") (class "Default")
      (node (ref "U4") (pin "2") (pinfunction "~{RI}_2") (pintype "passive"))
    )
    (net (code "65") (name "unconnected-(U4-~{RTS}-Pad19)") (class "Default")
      (node (ref "U4") (pin "19") (pinfunction "~{RTS}_19") (pintype "passive"))
    )
    (net (code "66") (name "unconnected-(U4-~{RXLED}_{slash}_CBUS1-Pad14)") (class "Default")
      (node (ref "U4") (pin "14") (pinfunction "~{RXLED}_/_CBUS1_14") (pintype "passive"))
    )
    (net (code "67") (name "unconnected-(U4-~{TXLED}_{slash}_CBUS2-Pad7)") (class "Default")
      (node (ref "U4") (pin "7") (pinfunction "~{TXLED}_/_CBUS2_7") (pintype "passive"))
    )
  )
)
